# xiao-waveshare.net
KiCad netlist of a schematic drawn in EAGLE
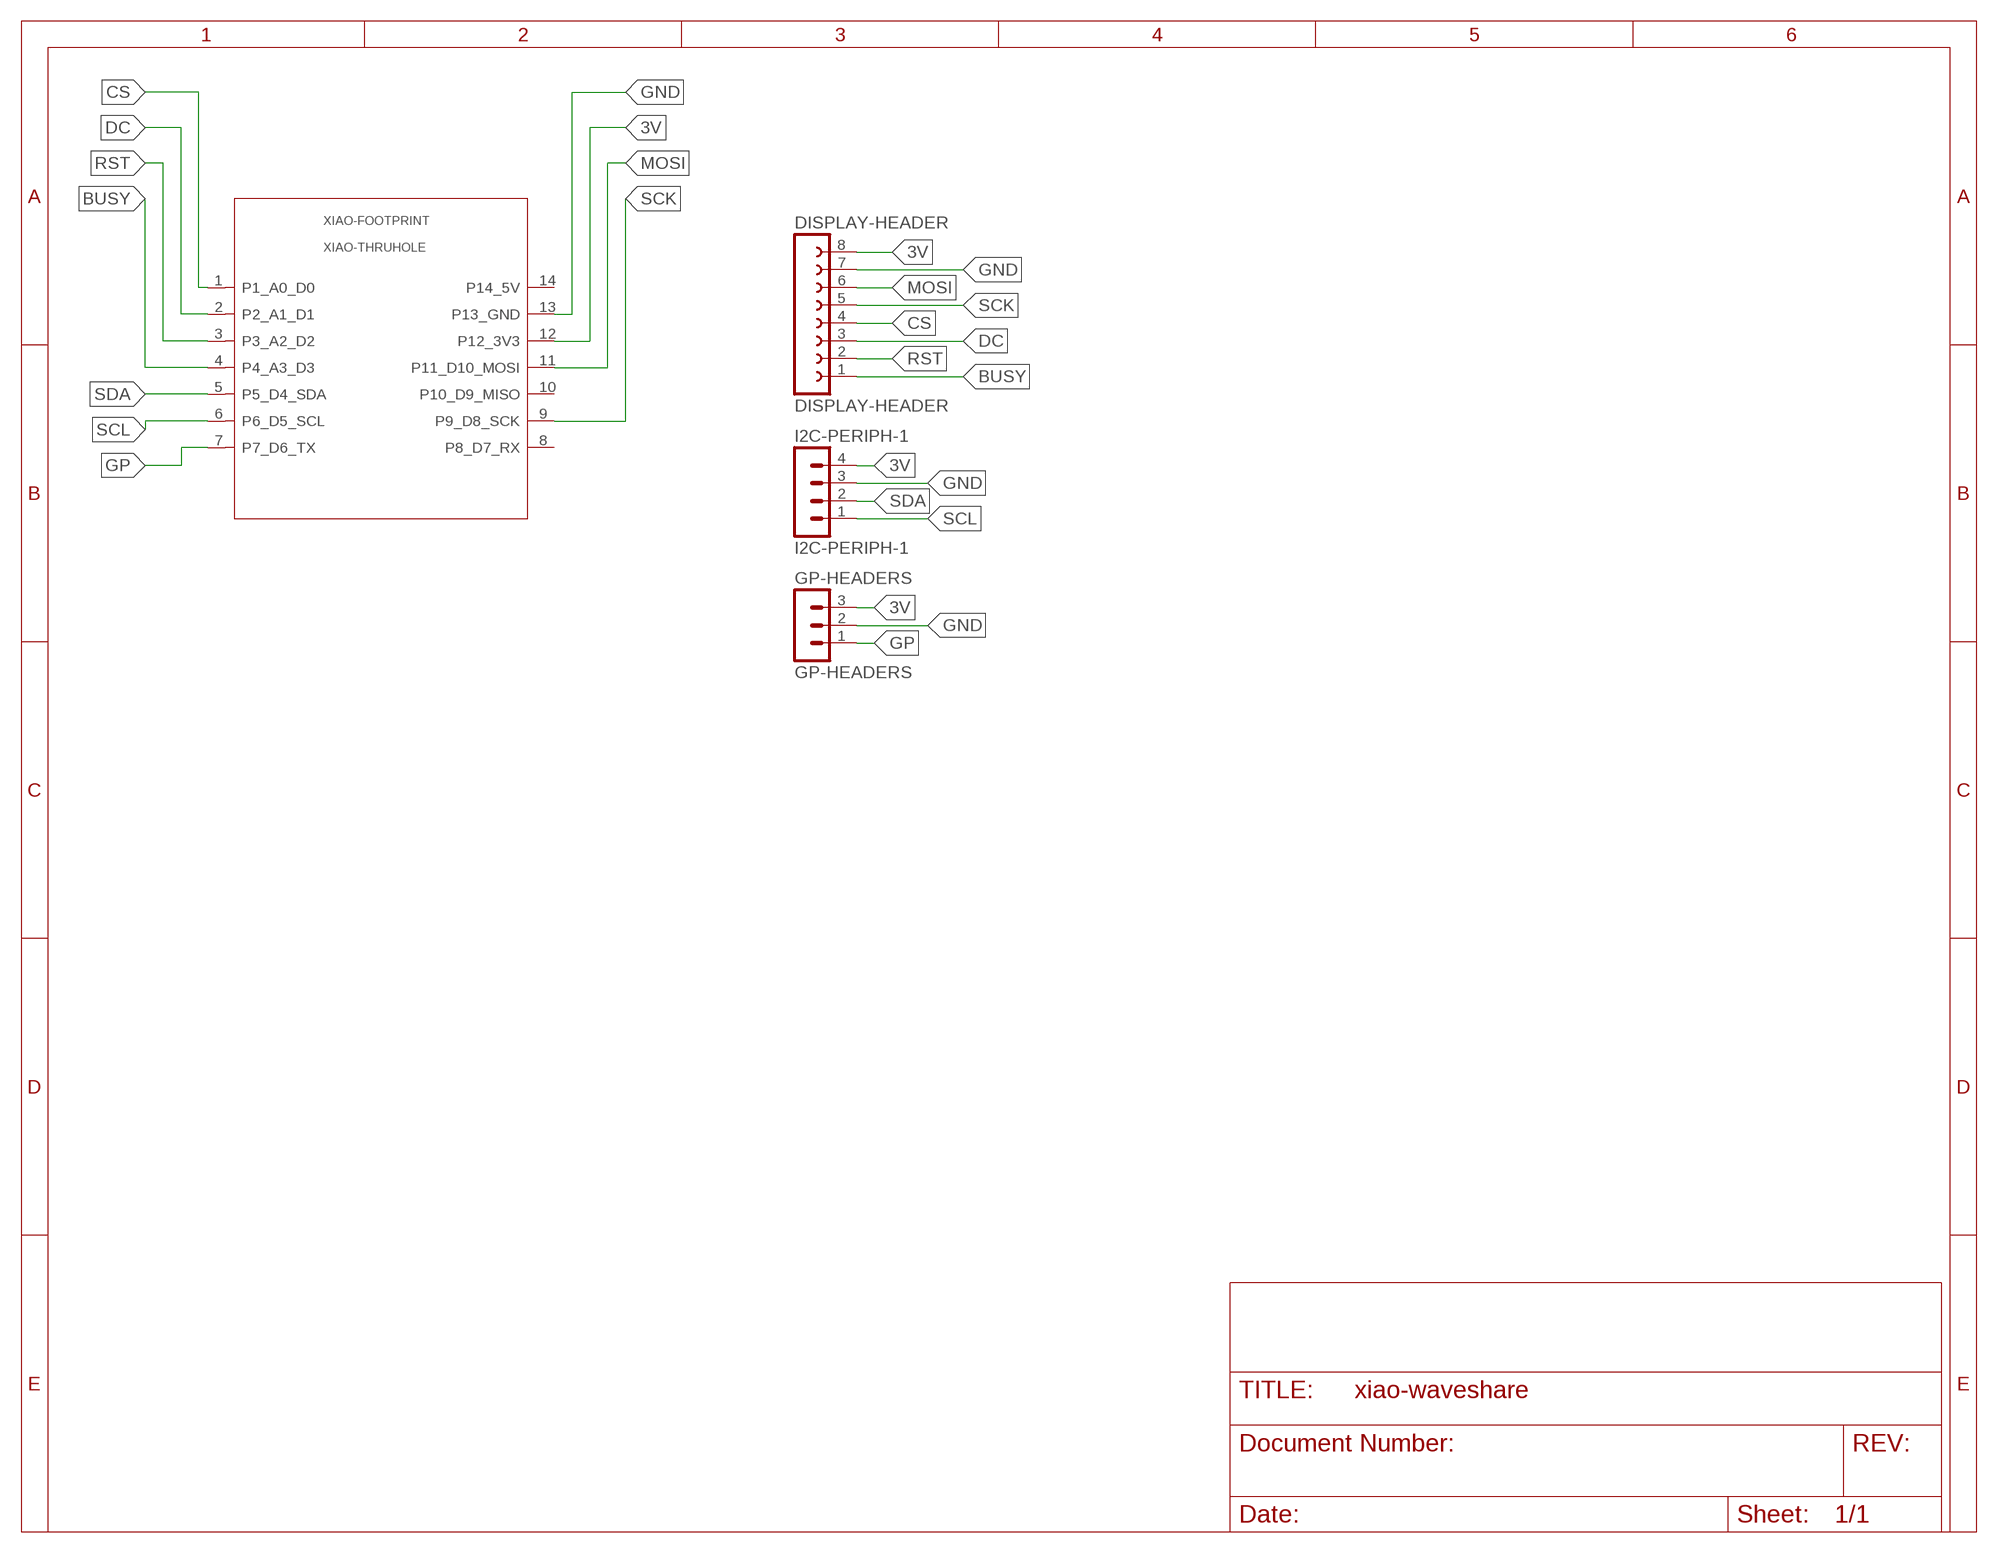
[diagram p0: schematic, sheet 1]

(export (version "E")
  (design (tool "Eeschema 10.0.6"))
  (components
    (comp (ref "DISPLAY-HEADER")
      (value "DISPLAY-HEADER")
      (footprint "eagle-import:FE08")
      (libsource (lib "eagle-import") (part "FE08-1"))
    )
    (comp (ref "GP-HEADERS")
      (value "GP-HEADERS")
      (footprint "eagle-import:MA03-1")
      (libsource (lib "eagle-import") (part "MA03-1"))
    )
    (comp (ref "I2C-PERIPH-1")
      (value "I2C-PERIPH-1")
      (footprint "eagle-import:MA04-1")
      (libsource (lib "eagle-import") (part "MA04-1"))
    )
    (comp (ref "XIAO-FOOTPRINT")
      (value "XIAO-THRUHOLE")
      (footprint "eagle-import:XIAO-GENERIC-THRUHOLE-MODULE14P-2.54-21X17.8MM")
      (libsource (lib "eagle-import") (part "XIAO-THRUHOLE"))
    )
  )
  (nets
    (net (code "1") (name "3V") (class "Default")
      (node (ref "DISPLAY-HEADER") (pin "8") (pinfunction "8_8") (pintype "passive"))
      (node (ref "GP-HEADERS") (pin "3") (pinfunction "3_3") (pintype "passive"))
      (node (ref "I2C-PERIPH-1") (pin "4") (pinfunction "4_4") (pintype "passive"))
      (node (ref "XIAO-FOOTPRINT") (pin "12") (pinfunction "P12_3V3_12") (pintype "bidirectional"))
    )
    (net (code "2") (name "BUSY") (class "Default")
      (node (ref "DISPLAY-HEADER") (pin "1") (pinfunction "1_1") (pintype "passive"))
      (node (ref "XIAO-FOOTPRINT") (pin "4") (pinfunction "P4_A3_D3_4") (pintype "bidirectional"))
    )
    (net (code "3") (name "CS") (class "Default")
      (node (ref "DISPLAY-HEADER") (pin "4") (pinfunction "4_4") (pintype "passive"))
      (node (ref "XIAO-FOOTPRINT") (pin "1") (pinfunction "P1_A0_D0_1") (pintype "bidirectional"))
    )
    (net (code "4") (name "DC") (class "Default")
      (node (ref "DISPLAY-HEADER") (pin "3") (pinfunction "3_3") (pintype "passive"))
      (node (ref "XIAO-FOOTPRINT") (pin "2") (pinfunction "P2_A1_D1_2") (pintype "bidirectional"))
    )
    (net (code "5") (name "GND") (class "Default")
      (node (ref "DISPLAY-HEADER") (pin "7") (pinfunction "7_7") (pintype "passive"))
      (node (ref "GP-HEADERS") (pin "2") (pinfunction "2_2") (pintype "passive"))
      (node (ref "I2C-PERIPH-1") (pin "3") (pinfunction "3_3") (pintype "passive"))
      (node (ref "XIAO-FOOTPRINT") (pin "13") (pinfunction "P13_GND_13") (pintype "bidirectional"))
    )
    (net (code "6") (name "GP") (class "Default")
      (node (ref "GP-HEADERS") (pin "1") (pinfunction "1_1") (pintype "passive"))
      (node (ref "XIAO-FOOTPRINT") (pin "7") (pinfunction "P7_D6_TX_7") (pintype "bidirectional"))
    )
    (net (code "7") (name "MOSI") (class "Default")
      (node (ref "DISPLAY-HEADER") (pin "6") (pinfunction "6_6") (pintype "passive"))
      (node (ref "XIAO-FOOTPRINT") (pin "11") (pinfunction "P11_D10_MOSI_11") (pintype "bidirectional"))
    )
    (net (code "8") (name "RST") (class "Default")
      (node (ref "DISPLAY-HEADER") (pin "2") (pinfunction "2_2") (pintype "passive"))
      (node (ref "XIAO-FOOTPRINT") (pin "3") (pinfunction "P3_A2_D2_3") (pintype "bidirectional"))
    )
    (net (code "9") (name "SCK") (class "Default")
      (node (ref "DISPLAY-HEADER") (pin "5") (pinfunction "5_5") (pintype "passive"))
      (node (ref "XIAO-FOOTPRINT") (pin "9") (pinfunction "P9_D8_SCK_9") (pintype "bidirectional"))
    )
    (net (code "10") (name "SCL") (class "Default")
      (node (ref "I2C-PERIPH-1") (pin "1") (pinfunction "1_1") (pintype "passive"))
      (node (ref "XIAO-FOOTPRINT") (pin "6") (pinfunction "P6_D5_SCL_6") (pintype "bidirectional"))
    )
    (net (code "11") (name "SDA") (class "Default")
      (node (ref "I2C-PERIPH-1") (pin "2") (pinfunction "2_2") (pintype "passive"))
      (node (ref "XIAO-FOOTPRINT") (pin "5") (pinfunction "P5_D4_SDA_5") (pintype "bidirectional"))
    )
    (net (code "12") (name "unconnected-(XIAO-FOOTPRINT-P8_D7_RX-Pad8)") (class "Default")
      (node (ref "XIAO-FOOTPRINT") (pin "8") (pinfunction "P8_D7_RX_8") (pintype "bidirectional"))
    )
    (net (code "13") (name "unconnected-(XIAO-FOOTPRINT-P10_D9_MISO-Pad10)") (class "Default")
      (node (ref "XIAO-FOOTPRINT") (pin "10") (pinfunction "P10_D9_MISO_10") (pintype "bidirectional"))
    )
    (net (code "14") (name "unconnected-(XIAO-FOOTPRINT-P14_5V-Pad14)") (class "Default")
      (node (ref "XIAO-FOOTPRINT") (pin "14") (pinfunction "P14_5V_14") (pintype "bidirectional"))
    )
  )
)
